# muxduino-shield.net
KiCad netlist of a schematic drawn in Altium Designer
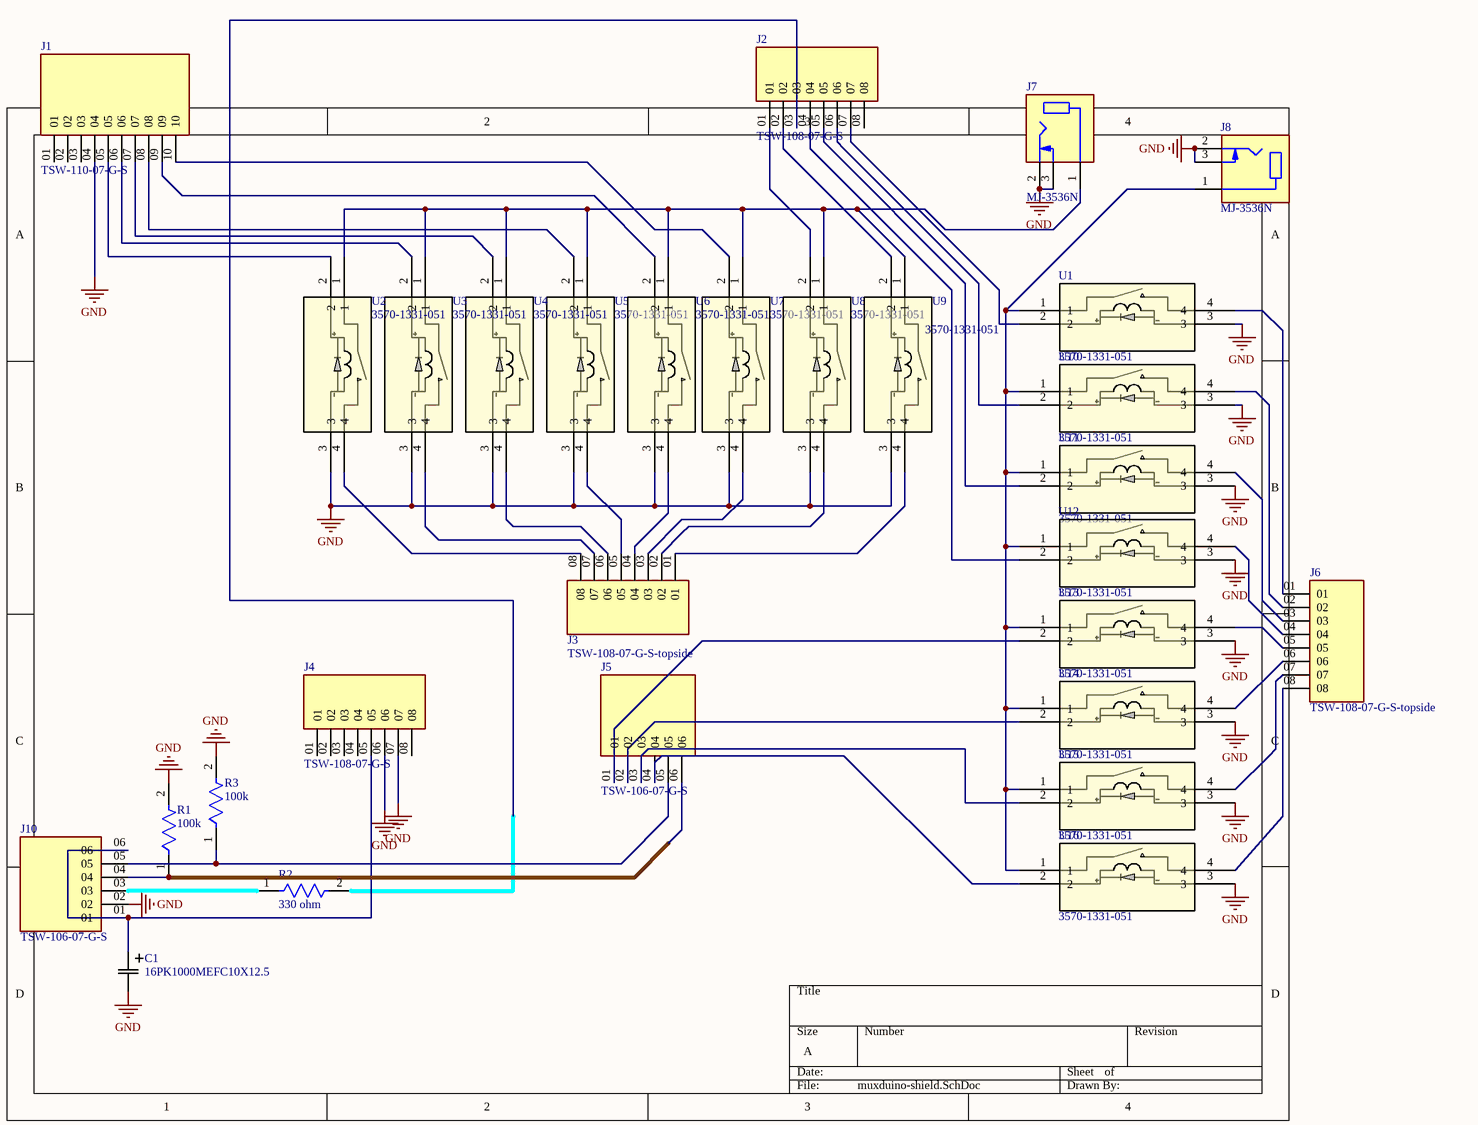
[diagram p0: muxduino-shield.SchDoc]

(export (version "E")
  (design (tool "Eeschema 10.0.6"))
  (components
    (comp (ref "C1")
      (value "16PK1000MEFC10X12.5")
      (footprint "CAP_PKPZ_10X12P5_LOW_RUB")
      (description "No Description Available")
      (fields (field (name "COPYRIGHT") "Copyright (C) 2024 Ultra Librarian. All rights reserved."))
      (libsource (lib "SchlibLafe") (part "16PK1000MEFC10X12.5"))
    )
    (comp (ref "J1")
      (value "TSW-110-07-G-S")
      (footprint "SAMTEC_TSW-110-07-G-S")
      (fields (field (name "MF") "Samtec Inc."))
      (libsource (lib "SchlibLafe") (part "TSW-110-07-G-S"))
    )
    (comp (ref "J2")
      (value "TSW-108-07-G-S")
      (footprint "SAMTEC_TSW-108-07-G-S")
      (description "TSW - Samtec 2.54mm Pin Header 10.92mm Overall Pin Length (07) - Fast Stock")
      (fields (field (name "MF") "Samtec Inc."))
      (libsource (lib "SchlibLafe") (part "TSW-108-07-G-S"))
    )
    (comp (ref "J3")
      (value "TSW-108-07-G-S-topside")
      (footprint "SAMTEC_TSW-108-07-G-S-topside")
      (description "TSW - Samtec 2.54mm Pin Header 10.92mm Overall Pin Length (07) - Fast Stock")
      (fields (field (name "MF") "Samtec Inc.") (field (name "MP") "TSW-108-07-G-S"))
      (libsource (lib "SchlibLafe") (part "TSW-108-07-G-S-topside"))
    )
    (comp (ref "J4")
      (value "TSW-108-07-G-S")
      (footprint "SAMTEC_TSW-108-07-G-S")
      (description "TSW - Samtec 2.54mm Pin Header 10.92mm Overall Pin Length (07) - Fast Stock")
      (fields (field (name "MF") "Samtec Inc."))
      (libsource (lib "SchlibLafe") (part "TSW-108-07-G-S"))
    )
    (comp (ref "J5")
      (value "TSW-106-07-G-S")
      (footprint "SAMTEC_TSW-106-07-G-S")
      (fields (field (name "MF") "Samtec Inc."))
      (libsource (lib "") (part "TSW-106-07-G-S_1"))
    )
    (comp (ref "J6")
      (value "TSW-108-07-G-S-topside")
      (footprint "SAMTEC_TSW-108-07-G-S-topside")
      (description "TSW - Samtec 2.54mm Pin Header 10.92mm Overall Pin Length (07) - Fast Stock")
      (fields (field (name "MF") "Samtec Inc.") (field (name "MP") "TSW-108-07-G-S"))
      (libsource (lib "") (part "TSW-108-07-G-S-topside_1"))
    )
    (comp (ref "J7")
      (value "MJ-3536N")
      (footprint "CUI_MJ-3536N")
      (fields (field (name "MF") "{'manufacturer': u'CUI Devices'}"))
      (libsource (lib "") (part "MJ-3536N_1"))
    )
    (comp (ref "J8")
      (value "MJ-3536N")
      (footprint "CUI_MJ-3536N")
      (fields (field (name "MF") "{'manufacturer': u'CUI Devices'}"))
      (libsource (lib "SchlibLafe") (part "MJ-3536N"))
    )
    (comp (ref "J10")
      (value "TSW-106-07-G-S")
      (footprint "SAMTEC_TSW-106-07-G-S")
      (fields (field (name "MF") "Samtec Inc."))
      (libsource (lib "SchlibLafe") (part "TSW-106-07-G-S"))
    )
    (comp (ref "R1")
      (value "100k")
      (footprint "FP-RLR07-MFG")
      (fields (field (name "TOLERANCE") "1%"))
      (libsource (lib "Altium Content Vault") (part "1029c3af85768c4190bb7ad29bc67b5"))
    )
    (comp (ref "R2")
      (value "330 ohm")
      (footprint "FP-RLR07-MFG")
      (fields (field (name "TOLERANCE") "1%"))
      (libsource (lib "Altium Content Vault") (part "1029c3af85768c4190bb7ad29bc67b5"))
    )
    (comp (ref "R3")
      (value "100k")
      (footprint "FP-RLR07-MFG")
      (fields (field (name "TOLERANCE") "1%"))
      (libsource (lib "Altium Content Vault") (part "1029c3af85768c4190bb7ad29bc67b5"))
    )
    (comp (ref "U1")
      (value "3570-1331-051")
      (footprint "SIP_3570-1331_COM")
      (description "No Description Available")
      (fields (field (name "COPYRIGHT") "Copyright (C) 2024 Ultra Librarian. All rights reserved."))
      (libsource (lib "") (part "3570-1331-051_1"))
    )
    (comp (ref "U2")
      (value "3570-1331-051")
      (footprint "SIP_3570-1331_COM")
      (description "No Description Available")
      (fields (field (name "COPYRIGHT") "Copyright (C) 2024 Ultra Librarian. All rights reserved."))
      (libsource (lib "SchlibAnna") (part "3570-1331-051"))
    )
    (comp (ref "U3")
      (value "3570-1331-051")
      (footprint "SIP_3570-1331_COM")
      (description "No Description Available")
      (fields (field (name "COPYRIGHT") "Copyright (C) 2024 Ultra Librarian. All rights reserved."))
      (libsource (lib "SchlibAnna") (part "3570-1331-051"))
    )
    (comp (ref "U4")
      (value "3570-1331-051")
      (footprint "SIP_3570-1331_COM")
      (description "No Description Available")
      (fields (field (name "COPYRIGHT") "Copyright (C) 2024 Ultra Librarian. All rights reserved."))
      (libsource (lib "SchlibAnna") (part "3570-1331-051"))
    )
    (comp (ref "U5")
      (value "3570-1331-051")
      (footprint "SIP_3570-1331_COM")
      (description "No Description Available")
      (fields (field (name "COPYRIGHT") "Copyright (C) 2024 Ultra Librarian. All rights reserved."))
      (libsource (lib "SchlibAnna") (part "3570-1331-051"))
    )
    (comp (ref "U6")
      (value "3570-1331-051")
      (footprint "SIP_3570-1331_COM")
      (description "No Description Available")
      (fields (field (name "COPYRIGHT") "Copyright (C) 2024 Ultra Librarian. All rights reserved."))
      (libsource (lib "SchlibAnna") (part "3570-1331-051"))
    )
    (comp (ref "U7")
      (value "3570-1331-051")
      (footprint "SIP_3570-1331_COM")
      (description "No Description Available")
      (fields (field (name "COPYRIGHT") "Copyright (C) 2024 Ultra Librarian. All rights reserved."))
      (libsource (lib "SchlibAnna") (part "3570-1331-051"))
    )
    (comp (ref "U8")
      (value "3570-1331-051")
      (footprint "SIP_3570-1331_COM")
      (description "No Description Available")
      (fields (field (name "COPYRIGHT") "Copyright (C) 2024 Ultra Librarian. All rights reserved."))
      (libsource (lib "SchlibAnna") (part "3570-1331-051"))
    )
    (comp (ref "U9")
      (value "3570-1331-051")
      (footprint "SIP_3570-1331_COM")
      (description "No Description Available")
      (fields (field (name "COPYRIGHT") "Copyright (C) 2024 Ultra Librarian. All rights reserved."))
      (libsource (lib "SchlibAnna") (part "3570-1331-051"))
    )
    (comp (ref "U10")
      (value "3570-1331-051")
      (footprint "SIP_3570-1331_COM")
      (description "No Description Available")
      (fields (field (name "COPYRIGHT") "Copyright (C) 2024 Ultra Librarian. All rights reserved."))
      (libsource (lib "") (part "3570-1331-051_1"))
    )
    (comp (ref "U11")
      (value "3570-1331-051")
      (footprint "SIP_3570-1331_COM")
      (description "No Description Available")
      (fields (field (name "COPYRIGHT") "Copyright (C) 2024 Ultra Librarian. All rights reserved."))
      (libsource (lib "") (part "3570-1331-051_1"))
    )
    (comp (ref "U12")
      (value "3570-1331-051")
      (footprint "SIP_3570-1331_COM")
      (description "No Description Available")
      (fields (field (name "COPYRIGHT") "Copyright (C) 2024 Ultra Librarian. All rights reserved."))
      (libsource (lib "") (part "3570-1331-051_1"))
    )
    (comp (ref "U13")
      (value "3570-1331-051")
      (footprint "SIP_3570-1331_COM")
      (description "No Description Available")
      (fields (field (name "COPYRIGHT") "Copyright (C) 2024 Ultra Librarian. All rights reserved."))
      (libsource (lib "") (part "3570-1331-051_1"))
    )
    (comp (ref "U14")
      (value "3570-1331-051")
      (footprint "SIP_3570-1331_COM")
      (description "No Description Available")
      (fields (field (name "COPYRIGHT") "Copyright (C) 2024 Ultra Librarian. All rights reserved."))
      (libsource (lib "") (part "3570-1331-051_1"))
    )
    (comp (ref "U15")
      (value "3570-1331-051")
      (footprint "SIP_3570-1331_COM")
      (description "No Description Available")
      (fields (field (name "COPYRIGHT") "Copyright (C) 2024 Ultra Librarian. All rights reserved."))
      (libsource (lib "") (part "3570-1331-051_1"))
    )
    (comp (ref "U16")
      (value "3570-1331-051")
      (footprint "SIP_3570-1331_COM")
      (description "No Description Available")
      (fields (field (name "COPYRIGHT") "Copyright (C) 2024 Ultra Librarian. All rights reserved."))
      (libsource (lib "") (part "3570-1331-051_1"))
    )
  )
  (nets
    (net (code "1") (name "GND") (class "Default")
      (node (ref "C1") (pin "2") (pinfunction "2_2") (pintype "passive"))
      (node (ref "J1") (pin "04") (pinfunction "04_04") (pintype "passive"))
      (node (ref "J10") (pin "02") (pinfunction "02_02") (pintype "passive"))
      (node (ref "J4") (pin "06") (pinfunction "06_06") (pintype "passive"))
      (node (ref "J4") (pin "07") (pinfunction "07_07") (pintype "passive"))
      (node (ref "J7") (pin "2") (pinfunction "2_2") (pintype "passive"))
      (node (ref "J7") (pin "3") (pinfunction "3_3") (pintype "passive"))
      (node (ref "J8") (pin "2") (pinfunction "2_2") (pintype "passive"))
      (node (ref "J8") (pin "3") (pinfunction "3_3") (pintype "passive"))
      (node (ref "R1") (pin "2") (pinfunction "2_2") (pintype "passive"))
      (node (ref "R3") (pin "2") (pinfunction "2_2") (pintype "passive"))
      (node (ref "U1") (pin "3") (pinfunction "3_3") (pintype "passive"))
      (node (ref "U10") (pin "3") (pinfunction "3_3") (pintype "passive"))
      (node (ref "U11") (pin "3") (pinfunction "3_3") (pintype "passive"))
      (node (ref "U12") (pin "3") (pinfunction "3_3") (pintype "passive"))
      (node (ref "U13") (pin "3") (pinfunction "3_3") (pintype "passive"))
      (node (ref "U14") (pin "3") (pinfunction "3_3") (pintype "passive"))
      (node (ref "U15") (pin "3") (pinfunction "3_3") (pintype "passive"))
      (node (ref "U16") (pin "3") (pinfunction "3_3") (pintype "passive"))
      (node (ref "U2") (pin "3") (pinfunction "3_3") (pintype "passive"))
      (node (ref "U3") (pin "3") (pinfunction "3_3") (pintype "passive"))
      (node (ref "U4") (pin "3") (pinfunction "3_3") (pintype "passive"))
      (node (ref "U5") (pin "3") (pinfunction "3_3") (pintype "passive"))
      (node (ref "U6") (pin "3") (pinfunction "3_3") (pintype "passive"))
      (node (ref "U7") (pin "3") (pinfunction "3_3") (pintype "passive"))
      (node (ref "U8") (pin "3") (pinfunction "3_3") (pintype "passive"))
      (node (ref "U9") (pin "3") (pinfunction "3_3") (pintype "passive"))
    )
    (net (code "2") (name "Net-(C1-Pad1)") (class "Default")
      (node (ref "C1") (pin "1") (pinfunction "1_1") (pintype "passive"))
      (node (ref "J10") (pin "01") (pinfunction "01_01") (pintype "passive"))
      (node (ref "J10") (pin "06") (pinfunction "06_06") (pintype "passive"))
      (node (ref "J4") (pin "05") (pinfunction "05_05") (pintype "passive"))
    )
    (net (code "3") (name "Net-(J1-Pad05)") (class "Default")
      (node (ref "J1") (pin "05") (pinfunction "05_05") (pintype "passive"))
      (node (ref "U2") (pin "2") (pinfunction "2_2") (pintype "passive"))
    )
    (net (code "4") (name "Net-(J1-Pad06)") (class "Default")
      (node (ref "J1") (pin "06") (pinfunction "06_06") (pintype "passive"))
      (node (ref "U3") (pin "2") (pinfunction "2_2") (pintype "passive"))
    )
    (net (code "5") (name "Net-(J1-Pad07)") (class "Default")
      (node (ref "J1") (pin "07") (pinfunction "07_07") (pintype "passive"))
      (node (ref "U4") (pin "2") (pinfunction "2_2") (pintype "passive"))
    )
    (net (code "6") (name "Net-(J1-Pad08)") (class "Default")
      (node (ref "J1") (pin "08") (pinfunction "08_08") (pintype "passive"))
      (node (ref "U5") (pin "2") (pinfunction "2_2") (pintype "passive"))
    )
    (net (code "7") (name "Net-(J1-Pad09)") (class "Default")
      (node (ref "J1") (pin "09") (pinfunction "09_09") (pintype "passive"))
      (node (ref "U6") (pin "2") (pinfunction "2_2") (pintype "passive"))
    )
    (net (code "8") (name "Net-(J1-Pad10)") (class "Default")
      (node (ref "J1") (pin "10") (pinfunction "10_10") (pintype "passive"))
      (node (ref "U7") (pin "2") (pinfunction "2_2") (pintype "passive"))
    )
    (net (code "9") (name "Net-(J2-Pad01)") (class "Default")
      (node (ref "J2") (pin "01") (pinfunction "01_01") (pintype "passive"))
      (node (ref "U8") (pin "2") (pinfunction "2_2") (pintype "passive"))
    )
    (net (code "10") (name "Net-(J2-Pad02)") (class "Default")
      (node (ref "J2") (pin "02") (pinfunction "02_02") (pintype "passive"))
      (node (ref "U9") (pin "2") (pinfunction "2_2") (pintype "passive"))
    )
    (net (code "11") (name "Net-(J2-Pad03)") (class "Default")
      (node (ref "J2") (pin "03") (pinfunction "03_03") (pintype "passive"))
      (node (ref "R2") (pin "2") (pinfunction "2_2") (pintype "passive"))
    )
    (net (code "12") (name "Net-(J2-Pad04)") (class "Default")
      (node (ref "J2") (pin "04") (pinfunction "04_04") (pintype "passive"))
      (node (ref "U12") (pin "2") (pinfunction "2_2") (pintype "passive"))
    )
    (net (code "13") (name "Net-(J2-Pad05)") (class "Default")
      (node (ref "J2") (pin "05") (pinfunction "05_05") (pintype "passive"))
      (node (ref "U11") (pin "2") (pinfunction "2_2") (pintype "passive"))
    )
    (net (code "14") (name "Net-(J2-Pad06)") (class "Default")
      (node (ref "J2") (pin "06") (pinfunction "06_06") (pintype "passive"))
      (node (ref "U10") (pin "2") (pinfunction "2_2") (pintype "passive"))
    )
    (net (code "15") (name "Net-(J2-Pad07)") (class "Default")
      (node (ref "J2") (pin "07") (pinfunction "07_07") (pintype "passive"))
      (node (ref "U1") (pin "2") (pinfunction "2_2") (pintype "passive"))
    )
    (net (code "16") (name "Net-(J3-Pad01)") (class "Default")
      (node (ref "J3") (pin "01") (pinfunction "01_01") (pintype "passive"))
      (node (ref "U9") (pin "4") (pinfunction "4_4") (pintype "passive"))
    )
    (net (code "17") (name "Net-(J3-Pad02)") (class "Default")
      (node (ref "J3") (pin "02") (pinfunction "02_02") (pintype "passive"))
      (node (ref "U8") (pin "4") (pinfunction "4_4") (pintype "passive"))
    )
    (net (code "18") (name "Net-(J3-Pad03)") (class "Default")
      (node (ref "J3") (pin "03") (pinfunction "03_03") (pintype "passive"))
      (node (ref "U7") (pin "4") (pinfunction "4_4") (pintype "passive"))
    )
    (net (code "19") (name "Net-(J3-Pad04)") (class "Default")
      (node (ref "J3") (pin "04") (pinfunction "04_04") (pintype "passive"))
      (node (ref "U6") (pin "4") (pinfunction "4_4") (pintype "passive"))
    )
    (net (code "20") (name "Net-(J3-Pad05)") (class "Default")
      (node (ref "J3") (pin "05") (pinfunction "05_05") (pintype "passive"))
      (node (ref "U5") (pin "4") (pinfunction "4_4") (pintype "passive"))
    )
    (net (code "21") (name "Net-(J3-Pad06)") (class "Default")
      (node (ref "J3") (pin "06") (pinfunction "06_06") (pintype "passive"))
      (node (ref "U4") (pin "4") (pinfunction "4_4") (pintype "passive"))
    )
    (net (code "22") (name "Net-(J3-Pad07)") (class "Default")
      (node (ref "J3") (pin "07") (pinfunction "07_07") (pintype "passive"))
      (node (ref "U3") (pin "4") (pinfunction "4_4") (pintype "passive"))
    )
    (net (code "23") (name "Net-(J3-Pad08)") (class "Default")
      (node (ref "J3") (pin "08") (pinfunction "08_08") (pintype "passive"))
      (node (ref "U2") (pin "4") (pinfunction "4_4") (pintype "passive"))
    )
    (net (code "24") (name "Net-(J5-Pad01)") (class "Default")
      (node (ref "J5") (pin "01") (pinfunction "01_01") (pintype "passive"))
      (node (ref "U13") (pin "2") (pinfunction "2_2") (pintype "passive"))
    )
    (net (code "25") (name "Net-(J5-Pad02)") (class "Default")
      (node (ref "J5") (pin "02") (pinfunction "02_02") (pintype "passive"))
      (node (ref "U14") (pin "2") (pinfunction "2_2") (pintype "passive"))
    )
    (net (code "26") (name "Net-(J5-Pad03)") (class "Default")
      (node (ref "J5") (pin "03") (pinfunction "03_03") (pintype "passive"))
      (node (ref "U15") (pin "2") (pinfunction "2_2") (pintype "passive"))
    )
    (net (code "27") (name "Net-(J5-Pad04)") (class "Default")
      (node (ref "J5") (pin "04") (pinfunction "04_04") (pintype "passive"))
      (node (ref "U16") (pin "2") (pinfunction "2_2") (pintype "passive"))
    )
    (net (code "28") (name "Net-(J6-Pad01)") (class "Default")
      (node (ref "J6") (pin "01") (pinfunction "01_01") (pintype "passive"))
      (node (ref "U1") (pin "4") (pinfunction "4_4") (pintype "passive"))
    )
    (net (code "29") (name "Net-(J6-Pad02)") (class "Default")
      (node (ref "J6") (pin "02") (pinfunction "02_02") (pintype "passive"))
      (node (ref "U10") (pin "4") (pinfunction "4_4") (pintype "passive"))
    )
    (net (code "30") (name "Net-(J6-Pad03)") (class "Default")
      (node (ref "J6") (pin "03") (pinfunction "03_03") (pintype "passive"))
      (node (ref "U11") (pin "4") (pinfunction "4_4") (pintype "passive"))
    )
    (net (code "31") (name "Net-(J6-Pad04)") (class "Default")
      (node (ref "J6") (pin "04") (pinfunction "04_04") (pintype "passive"))
      (node (ref "U12") (pin "4") (pinfunction "4_4") (pintype "passive"))
    )
    (net (code "32") (name "Net-(J6-Pad05)") (class "Default")
      (node (ref "J6") (pin "05") (pinfunction "05_05") (pintype "passive"))
      (node (ref "U13") (pin "4") (pinfunction "4_4") (pintype "passive"))
    )
    (net (code "33") (name "Net-(J6-Pad06)") (class "Default")
      (node (ref "J6") (pin "06") (pinfunction "06_06") (pintype "passive"))
      (node (ref "U14") (pin "4") (pinfunction "4_4") (pintype "passive"))
    )
    (net (code "34") (name "Net-(J6-Pad07)") (class "Default")
      (node (ref "J6") (pin "07") (pinfunction "07_07") (pintype "passive"))
      (node (ref "U15") (pin "4") (pinfunction "4_4") (pintype "passive"))
    )
    (net (code "35") (name "Net-(J6-Pad08)") (class "Default")
      (node (ref "J6") (pin "08") (pinfunction "08_08") (pintype "passive"))
      (node (ref "U16") (pin "4") (pinfunction "4_4") (pintype "passive"))
    )
    (net (code "36") (name "Net-(J7-Pad1)") (class "Default")
      (node (ref "J7") (pin "1") (pinfunction "1_1") (pintype "passive"))
      (node (ref "U2") (pin "1") (pinfunction "1_1") (pintype "passive"))
      (node (ref "U3") (pin "1") (pinfunction "1_1") (pintype "passive"))
      (node (ref "U4") (pin "1") (pinfunction "1_1") (pintype "passive"))
      (node (ref "U5") (pin "1") (pinfunction "1_1") (pintype "passive"))
      (node (ref "U6") (pin "1") (pinfunction "1_1") (pintype "passive"))
      (node (ref "U7") (pin "1") (pinfunction "1_1") (pintype "passive"))
      (node (ref "U8") (pin "1") (pinfunction "1_1") (pintype "passive"))
      (node (ref "U9") (pin "1") (pinfunction "1_1") (pintype "passive"))
    )
    (net (code "37") (name "Net-(J8-Pad1)") (class "Default")
      (node (ref "J8") (pin "1") (pinfunction "1_1") (pintype "passive"))
      (node (ref "U1") (pin "1") (pinfunction "1_1") (pintype "passive"))
      (node (ref "U10") (pin "1") (pinfunction "1_1") (pintype "passive"))
      (node (ref "U11") (pin "1") (pinfunction "1_1") (pintype "passive"))
      (node (ref "U12") (pin "1") (pinfunction "1_1") (pintype "passive"))
      (node (ref "U13") (pin "1") (pinfunction "1_1") (pintype "passive"))
      (node (ref "U14") (pin "1") (pinfunction "1_1") (pintype "passive"))
      (node (ref "U15") (pin "1") (pinfunction "1_1") (pintype "passive"))
      (node (ref "U16") (pin "1") (pinfunction "1_1") (pintype "passive"))
    )
    (net (code "38") (name "Net-(J10-Pad03)") (class "Default")
      (node (ref "J10") (pin "03") (pinfunction "03_03") (pintype "passive"))
      (node (ref "R2") (pin "1") (pinfunction "1_1") (pintype "passive"))
    )
    (net (code "39") (name "Net-(J10-Pad04)") (class "Default")
      (node (ref "J10") (pin "04") (pinfunction "04_04") (pintype "passive"))
      (node (ref "J5") (pin "06") (pinfunction "06_06") (pintype "passive"))
      (node (ref "R1") (pin "1") (pinfunction "1_1") (pintype "passive"))
    )
    (net (code "40") (name "Net-(J10-Pad05)") (class "Default")
      (node (ref "J10") (pin "05") (pinfunction "05_05") (pintype "passive"))
      (node (ref "J5") (pin "05") (pinfunction "05_05") (pintype "passive"))
      (node (ref "R3") (pin "1") (pinfunction "1_1") (pintype "passive"))
    )
    (net (code "41") (name "unconnected-(J1-Pad01)") (class "Default")
      (node (ref "J1") (pin "01") (pinfunction "01_01") (pintype "passive"))
    )
    (net (code "42") (name "unconnected-(J1-Pad02)") (class "Default")
      (node (ref "J1") (pin "02") (pinfunction "02_02") (pintype "passive"))
    )
    (net (code "43") (name "unconnected-(J1-Pad03)") (class "Default")
      (node (ref "J1") (pin "03") (pinfunction "03_03") (pintype "passive"))
    )
    (net (code "44") (name "unconnected-(J2-Pad08)") (class "Default")
      (node (ref "J2") (pin "08") (pinfunction "08_08") (pintype "passive"))
    )
    (net (code "45") (name "unconnected-(J4-Pad01)") (class "Default")
      (node (ref "J4") (pin "01") (pinfunction "01_01") (pintype "passive"))
    )
    (net (code "46") (name "unconnected-(J4-Pad02)") (class "Default")
      (node (ref "J4") (pin "02") (pinfunction "02_02") (pintype "passive"))
    )
    (net (code "47") (name "unconnected-(J4-Pad03)") (class "Default")
      (node (ref "J4") (pin "03") (pinfunction "03_03") (pintype "passive"))
    )
    (net (code "48") (name "unconnected-(J4-Pad04)") (class "Default")
      (node (ref "J4") (pin "04") (pinfunction "04_04") (pintype "passive"))
    )
    (net (code "49") (name "unconnected-(J4-Pad08)") (class "Default")
      (node (ref "J4") (pin "08") (pinfunction "08_08") (pintype "passive"))
    )
  )
)
